# tinyLIPO.net
KiCad netlist of a schematic drawn in EAGLE
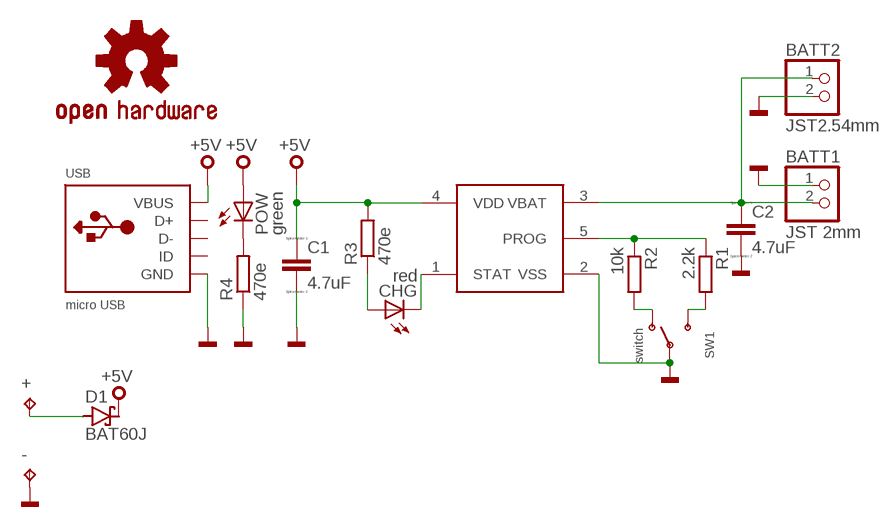
[diagram p0: schematic, sheet 1]

(export (version "E")
  (design (tool "Eeschema 10.0.6"))
  (components
    (comp (ref "+")
      (value "TPTP20SQ")
      (footprint "eagle-import:TP20SQ")
      (libsource (lib "eagle-import") (part "TPTP20SQ"))
    )
    (comp (ref "-")
      (value "TPTP20SQ")
      (footprint "eagle-import:TP20SQ")
      (libsource (lib "eagle-import") (part "TPTP20SQ"))
    )
    (comp (ref "BATT1")
      (value "JST 2mm")
      (footprint "eagle-import:JSTPH2")
      (libsource (lib "eagle-import") (part "JST_2PIN"))
    )
    (comp (ref "BATT2")
      (value "JST2.54mm")
      (footprint "eagle-import:1X02_OVAL")
      (libsource (lib "eagle-import") (part "HEADER-1X2"))
    )
    (comp (ref "C1")
      (value "4.7uF")
      (footprint "eagle-import:C0805")
      (libsource (lib "eagle-import") (part "C-EUC0805"))
    )
    (comp (ref "C2")
      (value "4.7uF")
      (footprint "eagle-import:C0805")
      (libsource (lib "eagle-import") (part "C-EUC0805"))
    )
    (comp (ref "CHG")
      (value "red")
      (footprint "eagle-import:CHIPLED_0805")
      (libsource (lib "eagle-import") (part "LEDCHIPLED_0805"))
    )
    (comp (ref "D1")
      (value "BAT60J")
      (footprint "eagle-import:SOD323_ST")
      (libsource (lib "eagle-import") (part "BAT60J"))
    )
    (comp (ref "IC1")
      (value "MCP73831")
      (footprint "eagle-import:SOT23-5")
      (libsource (lib "eagle-import") (part "MCP73831"))
    )
    (comp (ref "LOGO1")
      (value "OSHW-LOGOM")
      (footprint "eagle-import:OSHW-LOGO-M")
      (libsource (lib "eagle-import") (part "OSHW-LOGOM"))
    )
    (comp (ref "POW")
      (value "green")
      (footprint "eagle-import:CHIPLED_0805")
      (libsource (lib "eagle-import") (part "LEDCHIPLED_0805"))
    )
    (comp (ref "R1")
      (value "2.2k")
      (footprint "eagle-import:M0805")
      (libsource (lib "eagle-import") (part "R-EU_M0805"))
    )
    (comp (ref "R2")
      (value "10k")
      (footprint "eagle-import:M0805")
      (libsource (lib "eagle-import") (part "R-EU_M0805"))
    )
    (comp (ref "R3")
      (value "470e")
      (footprint "eagle-import:M0805")
      (libsource (lib "eagle-import") (part "R-EU_M0805"))
    )
    (comp (ref "R4")
      (value "470e")
      (footprint "eagle-import:M0805")
      (libsource (lib "eagle-import") (part "R-EU_M0805"))
    )
    (comp (ref "SW1")
      (value "switch")
      (footprint "eagle-import:SPDT_SMT_SSSS811101")
      (libsource (lib "eagle-import") (part "SWITCH_SPDT"))
    )
    (comp (ref "USB")
      (value "micro USB")
      (footprint "eagle-import:USB-MINIB_LARGER")
      (libsource (lib "eagle-import") (part "USBMINIBLARGE"))
    )
  )
  (nets
    (net (code "1") (name "+5V") (class "Default")
      (node (ref "C1") (pin "1") (pinfunction "1_1") (pintype "passive"))
      (node (ref "D1") (pin "C") (pinfunction "C_C") (pintype "passive"))
      (node (ref "IC1") (pin "4") (pinfunction "VDD_4") (pintype "bidirectional"))
      (node (ref "POW") (pin "A") (pinfunction "A_A") (pintype "passive"))
      (node (ref "R3") (pin "2") (pinfunction "2_2") (pintype "passive"))
      (node (ref "USB") (pin "VBUS") (pinfunction "VBUS_VBUS") (pintype "power_in"))
    )
    (net (code "2") (name "GND") (class "Default")
      (node (ref "-") (pin "TP") (pinfunction "TP_TP") (pintype "input"))
      (node (ref "BATT1") (pin "1") (pinfunction "1_1") (pintype "passive"))
      (node (ref "BATT2") (pin "2") (pinfunction "2_2") (pintype "passive"))
      (node (ref "C1") (pin "2") (pinfunction "2_2") (pintype "passive"))
      (node (ref "C2") (pin "2") (pinfunction "2_2") (pintype "passive"))
      (node (ref "IC1") (pin "2") (pinfunction "VSS_2") (pintype "bidirectional"))
      (node (ref "R4") (pin "1") (pinfunction "1_1") (pintype "passive"))
      (node (ref "SW1") (pin "B") (pinfunction "P_B") (pintype "passive"))
      (node (ref "USB") (pin "GND") (pinfunction "GND_GND") (pintype "power_in"))
    )
    (net (code "3") (name "Net-(+-PadTP)") (class "Default")
      (node (ref "+") (pin "TP") (pinfunction "TP_TP") (pintype "input"))
      (node (ref "D1") (pin "A") (pinfunction "A_A") (pintype "passive"))
    )
    (net (code "4") (name "Net-(CHG-PadA)") (class "Default")
      (node (ref "CHG") (pin "A") (pinfunction "A_A") (pintype "passive"))
      (node (ref "R3") (pin "1") (pinfunction "1_1") (pintype "passive"))
    )
    (net (code "5") (name "Net-(IC1-PROG)") (class "Default")
      (node (ref "IC1") (pin "5") (pinfunction "PROG_5") (pintype "bidirectional"))
      (node (ref "R1") (pin "1") (pinfunction "1_1") (pintype "passive"))
      (node (ref "R2") (pin "1") (pinfunction "1_1") (pintype "passive"))
    )
    (net (code "6") (name "Net-(IC1-STAT)") (class "Default")
      (node (ref "CHG") (pin "C") (pinfunction "C_C") (pintype "passive"))
      (node (ref "IC1") (pin "1") (pinfunction "STAT_1") (pintype "bidirectional"))
    )
    (net (code "7") (name "Net-(IC1-VBAT)") (class "Default")
      (node (ref "BATT1") (pin "2") (pinfunction "2_2") (pintype "passive"))
      (node (ref "BATT2") (pin "1") (pinfunction "1_1") (pintype "passive"))
      (node (ref "C2") (pin "1") (pinfunction "1_1") (pintype "passive"))
      (node (ref "IC1") (pin "3") (pinfunction "VBAT_3") (pintype "bidirectional"))
    )
    (net (code "8") (name "Net-(POW-PadC)") (class "Default")
      (node (ref "POW") (pin "C") (pinfunction "C_C") (pintype "passive"))
      (node (ref "R4") (pin "2") (pinfunction "2_2") (pintype "passive"))
    )
    (net (code "9") (name "Net-(SW1-O)") (class "Default")
      (node (ref "R2") (pin "2") (pinfunction "2_2") (pintype "passive"))
      (node (ref "SW1") (pin "A") (pinfunction "O_A") (pintype "passive"))
    )
    (net (code "10") (name "Net-(SW1-S)") (class "Default")
      (node (ref "R1") (pin "2") (pinfunction "2_2") (pintype "passive"))
      (node (ref "SW1") (pin "C") (pinfunction "S_C") (pintype "passive"))
    )
    (net (code "11") (name "unconnected-(USB-PadD+)") (class "Default")
      (node (ref "USB") (pin "D+") (pinfunction "D+_D+") (pintype "bidirectional"))
    )
    (net (code "12") (name "unconnected-(USB-PadD-)") (class "Default")
      (node (ref "USB") (pin "D-") (pinfunction "D-_D-") (pintype "bidirectional"))
    )
    (net (code "13") (name "unconnected-(USB-PadID)") (class "Default")
      (node (ref "USB") (pin "ID") (pinfunction "ID_ID") (pintype "bidirectional"))
    )
  )
)
